# commu.net
KiCad netlist of a schematic drawn in Altium Designer
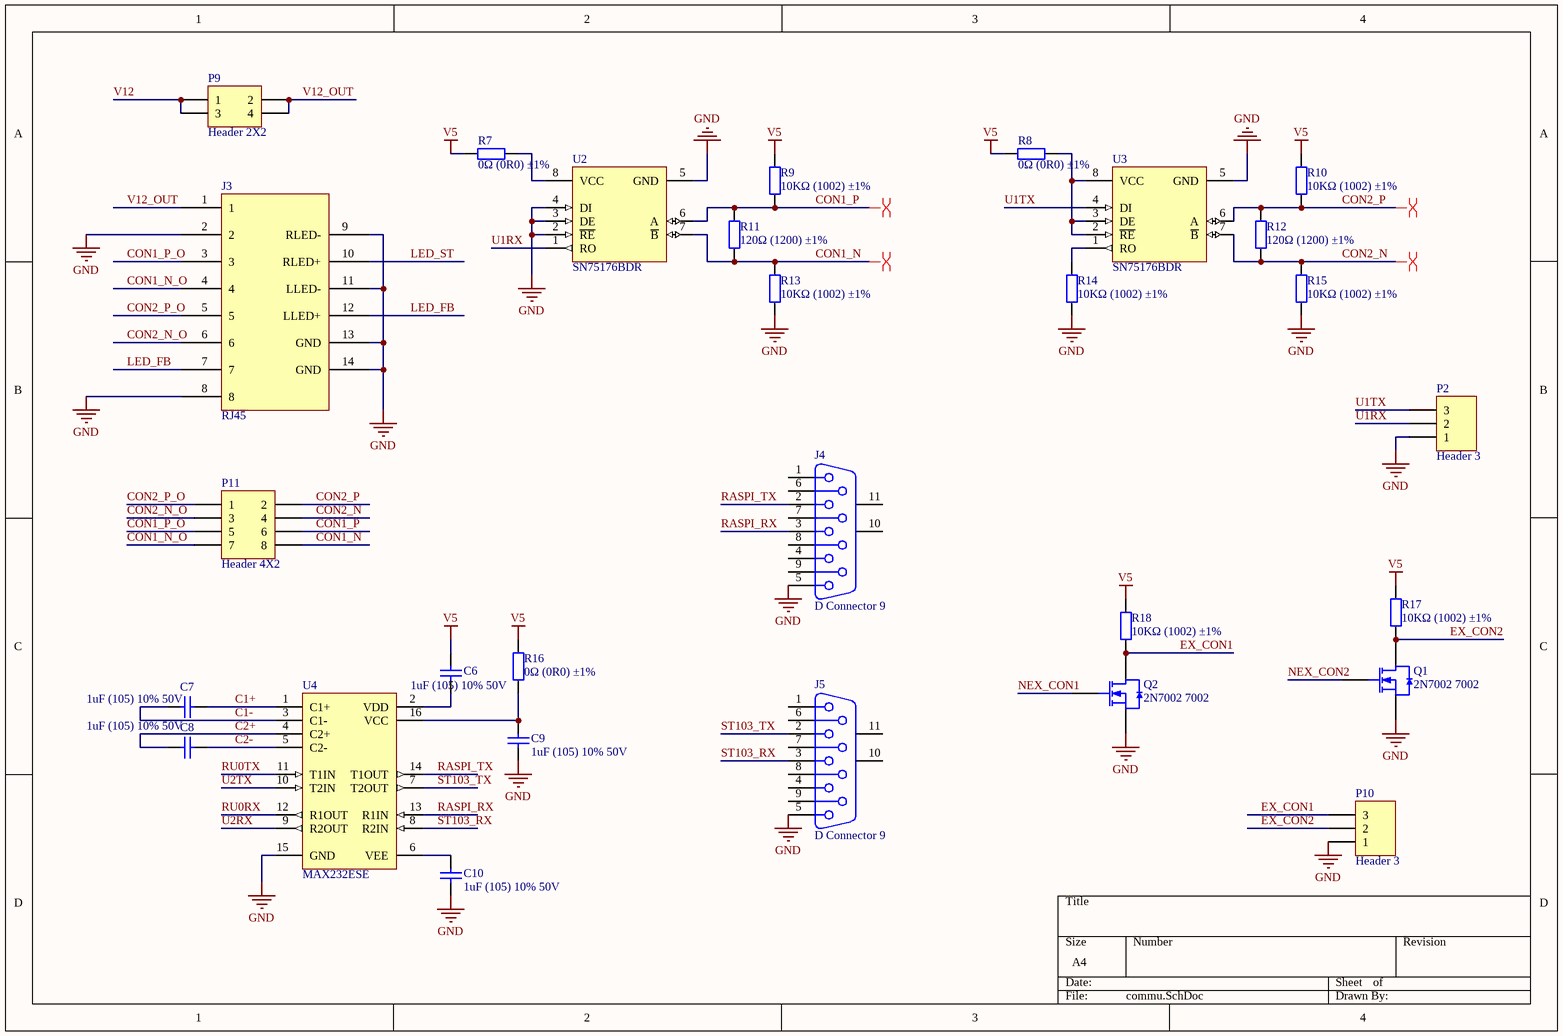
[diagram p0: commu.SchDoc]

(export (version "E")
  (design (tool "Eeschema 10.0.6"))
  (components
    (comp (ref "C6")
      (value "1uF (105) 10% 50V")
      (footprint "0603_C")
      (description "贴片电容")
      (libsource (lib "Miscellaneous Devices LC") (part "0603 1uF (105) 10% 50V"))
    )
    (comp (ref "C7")
      (value "1uF (105) 10% 50V")
      (footprint "0603_C")
      (description "贴片电容")
      (libsource (lib "Miscellaneous Devices LC") (part "0603 1uF (105) 10% 50V"))
    )
    (comp (ref "C8")
      (value "1uF (105) 10% 50V")
      (footprint "0603_C")
      (description "贴片电容")
      (libsource (lib "Miscellaneous Devices LC") (part "0603 1uF (105) 10% 50V"))
    )
    (comp (ref "C9")
      (value "1uF (105) 10% 50V")
      (footprint "0603_C")
      (description "贴片电容")
      (libsource (lib "Miscellaneous Devices LC") (part "0603 1uF (105) 10% 50V"))
    )
    (comp (ref "C10")
      (value "1uF (105) 10% 50V")
      (footprint "0603_C")
      (description "贴片电容")
      (libsource (lib "Miscellaneous Devices LC") (part "0603 1uF (105) 10% 50V"))
    )
    (comp (ref "J3") (value "RJ45") (footprint "RJ45_1") (libsource (lib "CHK-I") (part "RJ45_1")))
    (comp (ref "J4")
      (value "D Connector 9")
      (footprint "DSUB1.385-2H9")
      (description "Receptacle Assembly, 9 Position, Right Angle")
      (fields (field (name "PUBLISHER") "Altium Limited"))
      (libsource (lib "Miscellaneous Connectors") (part "D Connector 9"))
    )
    (comp (ref "J5")
      (value "D Connector 9")
      (footprint "DSUB1.385-2H9")
      (description "Receptacle Assembly, 9 Position, Right Angle")
      (fields (field (name "PUBLISHER") "Altium Limited"))
      (libsource (lib "Miscellaneous Connectors") (part "D Connector 9"))
    )
    (comp (ref "P2")
      (value "Header 3")
      (footprint "HDR1X3")
      (description "Header, 3-Pin")
      (fields (field (name "PUBLISHER") "Altium Limited"))
      (libsource (lib "Miscellaneous Connectors") (part "Header 3"))
    )
    (comp (ref "P9")
      (value "Header 2X2")
      (footprint "HDR2X2")
      (description "Header, 2-Pin, Dual row")
      (fields (field (name "PUBLISHER") "Altium Limited"))
      (libsource (lib "Miscellaneous Connectors") (part "Header 2X2"))
    )
    (comp (ref "P10")
      (value "Header 3")
      (footprint "HDR1X3")
      (description "Header, 3-Pin")
      (fields (field (name "PUBLISHER") "Altium Limited"))
      (libsource (lib "Miscellaneous Connectors") (part "Header 3"))
    )
    (comp (ref "P11")
      (value "Header 4X2")
      (footprint "HDR2X4")
      (description "Header, 4-Pin, Dual row")
      (fields (field (name "PUBLISHER") "Altium Limited"))
      (libsource (lib "Miscellaneous Connectors") (part "Header 4X2"))
    )
    (comp (ref "Q1")
      (value "2N7002 7002")
      (footprint "SOT-23(SOT-23-3)")
      (description "MOS(场效应管)")
      (libsource (lib "Miscellaneous Devices LC") (part "2N7002 7002"))
    )
    (comp (ref "Q2")
      (value "2N7002 7002")
      (footprint "SOT-23(SOT-23-3)")
      (description "MOS(场效应管)")
      (libsource (lib "Miscellaneous Devices LC") (part "2N7002 7002"))
    )
    (comp (ref "R7")
      (value "0Ω (0R0) ±1%")
      (footprint "1206_R")
      (description "贴片电阻")
      (libsource (lib "Miscellaneous Devices LC") (part "1206 0Ω (0R0) 1%"))
    )
    (comp (ref "R8")
      (value "0Ω (0R0) ±1%")
      (footprint "1206_R")
      (description "贴片电阻")
      (libsource (lib "Miscellaneous Devices LC") (part "1206 0Ω (0R0) 1%"))
    )
    (comp (ref "R9")
      (value "10KΩ (1002) ±1%")
      (footprint "0603_R")
      (description "贴片电阻")
      (libsource (lib "Miscellaneous Devices LC") (part "0603 10KΩ (1002) 1%"))
    )
    (comp (ref "R10")
      (value "10KΩ (1002) ±1%")
      (footprint "0603_R")
      (description "贴片电阻")
      (libsource (lib "Miscellaneous Devices LC") (part "0603 10KΩ (1002) 1%"))
    )
    (comp (ref "R11")
      (value "120Ω (1200) ±1%")
      (footprint "0603_R")
      (description "贴片电阻")
      (libsource (lib "Miscellaneous Devices LC") (part "0603 120Ω (1200) 1%"))
    )
    (comp (ref "R12")
      (value "120Ω (1200) ±1%")
      (footprint "0603_R")
      (description "贴片电阻")
      (libsource (lib "Miscellaneous Devices LC") (part "0603 120Ω (1200) 1%"))
    )
    (comp (ref "R13")
      (value "10KΩ (1002) ±1%")
      (footprint "0603_R")
      (description "贴片电阻")
      (libsource (lib "Miscellaneous Devices LC") (part "0603 10KΩ (1002) 1%"))
    )
    (comp (ref "R14")
      (value "10KΩ (1002) ±1%")
      (footprint "0603_R")
      (description "贴片电阻")
      (libsource (lib "Miscellaneous Devices LC") (part "0603 10KΩ (1002) 1%"))
    )
    (comp (ref "R15")
      (value "10KΩ (1002) ±1%")
      (footprint "0603_R")
      (description "贴片电阻")
      (libsource (lib "Miscellaneous Devices LC") (part "0603 10KΩ (1002) 1%"))
    )
    (comp (ref "R16")
      (value "0Ω (0R0) ±1%")
      (footprint "1206_R")
      (description "贴片电阻")
      (libsource (lib "") (part "1206 0Ω (0R0) 1%_1"))
    )
    (comp (ref "R17")
      (value "10KΩ (1002) ±1%")
      (footprint "0603_R")
      (description "贴片电阻")
      (libsource (lib "Miscellaneous Devices LC") (part "0603 10KΩ (1002) 1%"))
    )
    (comp (ref "R18")
      (value "10KΩ (1002) ±1%")
      (footprint "0603_R")
      (description "贴片电阻")
      (libsource (lib "Miscellaneous Devices LC") (part "0603 10KΩ (1002) 1%"))
    )
    (comp (ref "U2")
      (value "SN75176BDR")
      (footprint "SOIC-8_150mil")
      (description "RS-485/RS-422")
      (libsource (lib "Miscellaneous Devices LC") (part "SN75176BDR_[C7063]"))
    )
    (comp (ref "U3")
      (value "SN75176BDR")
      (footprint "SOIC-8_150mil")
      (description "RS-485/RS-422")
      (libsource (lib "Miscellaneous Devices LC") (part "SN75176BDR_[C7063]"))
    )
    (comp (ref "U4")
      (value "MAX232ESE")
      (footprint "SOIC-16_150mil")
      (description "RS232")
      (libsource (lib "Miscellaneous Devices LC") (part "MAX232ESE_[C26860]"))
    )
  )
  (nets
    (net (code "1") (name "/C1+") (class "Default")
      (node (ref "C7") (pin "2") (pinfunction "2_2") (pintype "passive"))
      (node (ref "U4") (pin "1") (pinfunction "C1+_1") (pintype "passive"))
    )
    (net (code "2") (name "/C1-") (class "Default")
      (node (ref "C7") (pin "1") (pinfunction "1_1") (pintype "passive"))
      (node (ref "U4") (pin "3") (pinfunction "C1-_3") (pintype "passive"))
    )
    (net (code "3") (name "/C2+") (class "Default")
      (node (ref "C8") (pin "1") (pinfunction "1_1") (pintype "passive"))
      (node (ref "U4") (pin "4") (pinfunction "C2+_4") (pintype "passive"))
    )
    (net (code "4") (name "/C2-") (class "Default")
      (node (ref "C8") (pin "2") (pinfunction "2_2") (pintype "passive"))
      (node (ref "U4") (pin "5") (pinfunction "C2-_5") (pintype "passive"))
    )
    (net (code "5") (name "/CON1_N") (class "Default")
      (node (ref "P11") (pin "8") (pinfunction "8_8") (pintype "passive"))
      (node (ref "R11") (pin "1") (pinfunction "1_1") (pintype "passive"))
      (node (ref "R13") (pin "2") (pinfunction "2_2") (pintype "passive"))
      (node (ref "U2") (pin "7") (pinfunction "~{B}_7") (pintype "bidirectional"))
    )
    (net (code "6") (name "/CON1_N_O") (class "Default")
      (node (ref "J3") (pin "4") (pinfunction "4_4") (pintype "passive"))
      (node (ref "P11") (pin "7") (pinfunction "7_7") (pintype "passive"))
    )
    (net (code "7") (name "/CON1_P") (class "Default")
      (node (ref "P11") (pin "6") (pinfunction "6_6") (pintype "passive"))
      (node (ref "R11") (pin "2") (pinfunction "2_2") (pintype "passive"))
      (node (ref "R9") (pin "1") (pinfunction "1_1") (pintype "passive"))
      (node (ref "U2") (pin "6") (pinfunction "A_6") (pintype "bidirectional"))
    )
    (net (code "8") (name "/CON1_P_O") (class "Default")
      (node (ref "J3") (pin "3") (pinfunction "3_3") (pintype "passive"))
      (node (ref "P11") (pin "5") (pinfunction "5_5") (pintype "passive"))
    )
    (net (code "9") (name "/CON2_N") (class "Default")
      (node (ref "P11") (pin "4") (pinfunction "4_4") (pintype "passive"))
      (node (ref "R12") (pin "1") (pinfunction "1_1") (pintype "passive"))
      (node (ref "R15") (pin "2") (pinfunction "2_2") (pintype "passive"))
      (node (ref "U3") (pin "7") (pinfunction "~{B}_7") (pintype "bidirectional"))
    )
    (net (code "10") (name "/CON2_N_O") (class "Default")
      (node (ref "J3") (pin "6") (pinfunction "6_6") (pintype "passive"))
      (node (ref "P11") (pin "3") (pinfunction "3_3") (pintype "passive"))
    )
    (net (code "11") (name "/CON2_P") (class "Default")
      (node (ref "P11") (pin "2") (pinfunction "2_2") (pintype "passive"))
      (node (ref "R10") (pin "1") (pinfunction "1_1") (pintype "passive"))
      (node (ref "R12") (pin "2") (pinfunction "2_2") (pintype "passive"))
      (node (ref "U3") (pin "6") (pinfunction "A_6") (pintype "bidirectional"))
    )
    (net (code "12") (name "/CON2_P_O") (class "Default")
      (node (ref "J3") (pin "5") (pinfunction "5_5") (pintype "passive"))
      (node (ref "P11") (pin "1") (pinfunction "1_1") (pintype "passive"))
    )
    (net (code "13") (name "/EX_CON1") (class "Default")
      (node (ref "P10") (pin "3") (pinfunction "3_3") (pintype "passive"))
      (node (ref "Q2") (pin "3") (pinfunction "D_3") (pintype "passive"))
      (node (ref "R18") (pin "1") (pinfunction "1_1") (pintype "passive"))
    )
    (net (code "14") (name "/EX_CON2") (class "Default")
      (node (ref "P10") (pin "2") (pinfunction "2_2") (pintype "passive"))
      (node (ref "Q1") (pin "3") (pinfunction "D_3") (pintype "passive"))
      (node (ref "R17") (pin "1") (pinfunction "1_1") (pintype "passive"))
    )
    (net (code "15") (name "/LED_FB") (class "Default")
      (node (ref "J3") (pin "12") (pinfunction "LLED+_12") (pintype "passive"))
      (node (ref "J3") (pin "7") (pinfunction "7_7") (pintype "passive"))
    )
    (net (code "16") (name "/LED_ST") (class "Default")
      (node (ref "J3") (pin "10") (pinfunction "RLED+_10") (pintype "passive"))
    )
    (net (code "17") (name "/NEX_CON1") (class "Default")
      (node (ref "Q2") (pin "1") (pinfunction "G_1") (pintype "passive"))
    )
    (net (code "18") (name "/NEX_CON2") (class "Default")
      (node (ref "Q1") (pin "1") (pinfunction "G_1") (pintype "passive"))
    )
    (net (code "19") (name "/RASPI_RX") (class "Default")
      (node (ref "J4") (pin "3") (pinfunction "3_3") (pintype "passive"))
      (node (ref "U4") (pin "13") (pinfunction "R1IN_13") (pintype "input"))
    )
    (net (code "20") (name "/RASPI_TX") (class "Default")
      (node (ref "J4") (pin "2") (pinfunction "2_2") (pintype "passive"))
      (node (ref "U4") (pin "14") (pinfunction "T1OUT_14") (pintype "output"))
    )
    (net (code "21") (name "/RU0RX") (class "Default")
      (node (ref "U4") (pin "12") (pinfunction "R1OUT_12") (pintype "output"))
    )
    (net (code "22") (name "/RU0TX") (class "Default")
      (node (ref "U4") (pin "11") (pinfunction "T1IN_11") (pintype "input"))
    )
    (net (code "23") (name "/ST103_RX") (class "Default")
      (node (ref "J5") (pin "3") (pinfunction "3_3") (pintype "passive"))
      (node (ref "U4") (pin "8") (pinfunction "R2IN_8") (pintype "input"))
    )
    (net (code "24") (name "/ST103_TX") (class "Default")
      (node (ref "J5") (pin "2") (pinfunction "2_2") (pintype "passive"))
      (node (ref "U4") (pin "7") (pinfunction "T2OUT_7") (pintype "output"))
    )
    (net (code "25") (name "/U1RX") (class "Default")
      (node (ref "P2") (pin "2") (pinfunction "2_2") (pintype "passive"))
      (node (ref "U2") (pin "1") (pinfunction "RO_1") (pintype "output"))
    )
    (net (code "26") (name "/U1TX") (class "Default")
      (node (ref "P2") (pin "3") (pinfunction "3_3") (pintype "passive"))
      (node (ref "U3") (pin "4") (pinfunction "DI_4") (pintype "input"))
    )
    (net (code "27") (name "/U2RX") (class "Default")
      (node (ref "U4") (pin "9") (pinfunction "R2OUT_9") (pintype "output"))
    )
    (net (code "28") (name "/U2TX") (class "Default")
      (node (ref "U4") (pin "10") (pinfunction "T2IN_10") (pintype "input"))
    )
    (net (code "29") (name "/V12") (class "Default")
      (node (ref "P9") (pin "1") (pinfunction "1_1") (pintype "passive"))
      (node (ref "P9") (pin "3") (pinfunction "3_3") (pintype "passive"))
    )
    (net (code "30") (name "/V12_OUT") (class "Default")
      (node (ref "J3") (pin "1") (pinfunction "1_1") (pintype "passive"))
      (node (ref "P9") (pin "2") (pinfunction "2_2") (pintype "passive"))
      (node (ref "P9") (pin "4") (pinfunction "4_4") (pintype "passive"))
    )
    (net (code "31") (name "GND") (class "Default")
      (node (ref "C10") (pin "1") (pinfunction "1_1") (pintype "passive"))
      (node (ref "C9") (pin "1") (pinfunction "1_1") (pintype "passive"))
      (node (ref "J3") (pin "11") (pinfunction "LLED-_11") (pintype "passive"))
      (node (ref "J3") (pin "13") (pinfunction "GND_13") (pintype "passive"))
      (node (ref "J3") (pin "14") (pinfunction "GND_14") (pintype "passive"))
      (node (ref "J3") (pin "2") (pinfunction "2_2") (pintype "passive"))
      (node (ref "J3") (pin "8") (pinfunction "8_8") (pintype "passive"))
      (node (ref "J3") (pin "9") (pinfunction "RLED-_9") (pintype "passive"))
      (node (ref "J4") (pin "5") (pinfunction "5_5") (pintype "passive"))
      (node (ref "J5") (pin "5") (pinfunction "5_5") (pintype "passive"))
      (node (ref "P10") (pin "1") (pinfunction "1_1") (pintype "passive"))
      (node (ref "P2") (pin "1") (pinfunction "1_1") (pintype "passive"))
      (node (ref "Q1") (pin "2") (pinfunction "S_2") (pintype "passive"))
      (node (ref "Q2") (pin "2") (pinfunction "S_2") (pintype "passive"))
      (node (ref "R13") (pin "1") (pinfunction "1_1") (pintype "passive"))
      (node (ref "R14") (pin "1") (pinfunction "1_1") (pintype "passive"))
      (node (ref "R15") (pin "1") (pinfunction "1_1") (pintype "passive"))
      (node (ref "U2") (pin "2") (pinfunction "~{RE}_2") (pintype "input"))
      (node (ref "U2") (pin "3") (pinfunction "DE_3") (pintype "input"))
      (node (ref "U2") (pin "4") (pinfunction "DI_4") (pintype "input"))
      (node (ref "U2") (pin "5") (pinfunction "GND_5") (pintype "power_in"))
      (node (ref "U3") (pin "5") (pinfunction "GND_5") (pintype "power_in"))
      (node (ref "U4") (pin "15") (pinfunction "GND_15") (pintype "power_in"))
    )
    (net (code "32") (name "Net-(U2-VCC)") (class "Default")
      (node (ref "R7") (pin "2") (pinfunction "2_2") (pintype "passive"))
      (node (ref "U2") (pin "8") (pinfunction "VCC_8") (pintype "power_in"))
    )
    (net (code "33") (name "Net-(U3-DE)") (class "Default")
      (node (ref "R8") (pin "2") (pinfunction "2_2") (pintype "passive"))
      (node (ref "U3") (pin "2") (pinfunction "~{RE}_2") (pintype "input"))
      (node (ref "U3") (pin "3") (pinfunction "DE_3") (pintype "input"))
      (node (ref "U3") (pin "8") (pinfunction "VCC_8") (pintype "power_in"))
    )
    (net (code "34") (name "Net-(U3-RO)") (class "Default")
      (node (ref "R14") (pin "2") (pinfunction "2_2") (pintype "passive"))
      (node (ref "U3") (pin "1") (pinfunction "RO_1") (pintype "output"))
    )
    (net (code "35") (name "Net-(U4-VCC)") (class "Default")
      (node (ref "C9") (pin "2") (pinfunction "2_2") (pintype "passive"))
      (node (ref "R16") (pin "1") (pinfunction "1_1") (pintype "passive"))
      (node (ref "U4") (pin "16") (pinfunction "VCC_16") (pintype "power_in"))
    )
    (net (code "36") (name "Net-(U4-VDD)") (class "Default")
      (node (ref "C6") (pin "1") (pinfunction "1_1") (pintype "passive"))
      (node (ref "U4") (pin "2") (pinfunction "VDD_2") (pintype "power_in"))
    )
    (net (code "37") (name "Net-(U4-VEE)") (class "Default")
      (node (ref "C10") (pin "2") (pinfunction "2_2") (pintype "passive"))
      (node (ref "U4") (pin "6") (pinfunction "VEE_6") (pintype "power_in"))
    )
    (net (code "38") (name "V5") (class "Default")
      (node (ref "C6") (pin "2") (pinfunction "2_2") (pintype "passive"))
      (node (ref "R10") (pin "2") (pinfunction "2_2") (pintype "passive"))
      (node (ref "R16") (pin "2") (pinfunction "2_2") (pintype "passive"))
      (node (ref "R17") (pin "2") (pinfunction "2_2") (pintype "passive"))
      (node (ref "R18") (pin "2") (pinfunction "2_2") (pintype "passive"))
      (node (ref "R7") (pin "1") (pinfunction "1_1") (pintype "passive"))
      (node (ref "R8") (pin "1") (pinfunction "1_1") (pintype "passive"))
      (node (ref "R9") (pin "2") (pinfunction "2_2") (pintype "passive"))
    )
    (net (code "39") (name "unconnected-(J4-MH1-Pad10)") (class "Default")
      (node (ref "J4") (pin "10") (pinfunction "MH1_10") (pintype "passive"))
    )
    (net (code "40") (name "unconnected-(J4-MH2-Pad11)") (class "Default")
      (node (ref "J4") (pin "11") (pinfunction "MH2_11") (pintype "passive"))
    )
    (net (code "41") (name "unconnected-(J4-Pad1)") (class "Default")
      (node (ref "J4") (pin "1") (pinfunction "1_1") (pintype "passive"))
    )
    (net (code "42") (name "unconnected-(J4-Pad4)") (class "Default")
      (node (ref "J4") (pin "4") (pinfunction "4_4") (pintype "passive"))
    )
    (net (code "43") (name "unconnected-(J4-Pad6)") (class "Default")
      (node (ref "J4") (pin "6") (pinfunction "6_6") (pintype "passive"))
    )
    (net (code "44") (name "unconnected-(J4-Pad7)") (class "Default")
      (node (ref "J4") (pin "7") (pinfunction "7_7") (pintype "passive"))
    )
    (net (code "45") (name "unconnected-(J4-Pad8)") (class "Default")
      (node (ref "J4") (pin "8") (pinfunction "8_8") (pintype "passive"))
    )
    (net (code "46") (name "unconnected-(J4-Pad9)") (class "Default")
      (node (ref "J4") (pin "9") (pinfunction "9_9") (pintype "passive"))
    )
    (net (code "47") (name "unconnected-(J5-MH1-Pad10)") (class "Default")
      (node (ref "J5") (pin "10") (pinfunction "MH1_10") (pintype "passive"))
    )
    (net (code "48") (name "unconnected-(J5-MH2-Pad11)") (class "Default")
      (node (ref "J5") (pin "11") (pinfunction "MH2_11") (pintype "passive"))
    )
    (net (code "49") (name "unconnected-(J5-Pad1)") (class "Default")
      (node (ref "J5") (pin "1") (pinfunction "1_1") (pintype "passive"))
    )
    (net (code "50") (name "unconnected-(J5-Pad4)") (class "Default")
      (node (ref "J5") (pin "4") (pinfunction "4_4") (pintype "passive"))
    )
    (net (code "51") (name "unconnected-(J5-Pad6)") (class "Default")
      (node (ref "J5") (pin "6") (pinfunction "6_6") (pintype "passive"))
    )
    (net (code "52") (name "unconnected-(J5-Pad7)") (class "Default")
      (node (ref "J5") (pin "7") (pinfunction "7_7") (pintype "passive"))
    )
    (net (code "53") (name "unconnected-(J5-Pad8)") (class "Default")
      (node (ref "J5") (pin "8") (pinfunction "8_8") (pintype "passive"))
    )
    (net (code "54") (name "unconnected-(J5-Pad9)") (class "Default")
      (node (ref "J5") (pin "9") (pinfunction "9_9") (pintype "passive"))
    )
  )
)
